# Module_I2C_Servo.net
KiCad netlist of a schematic drawn in EAGLE
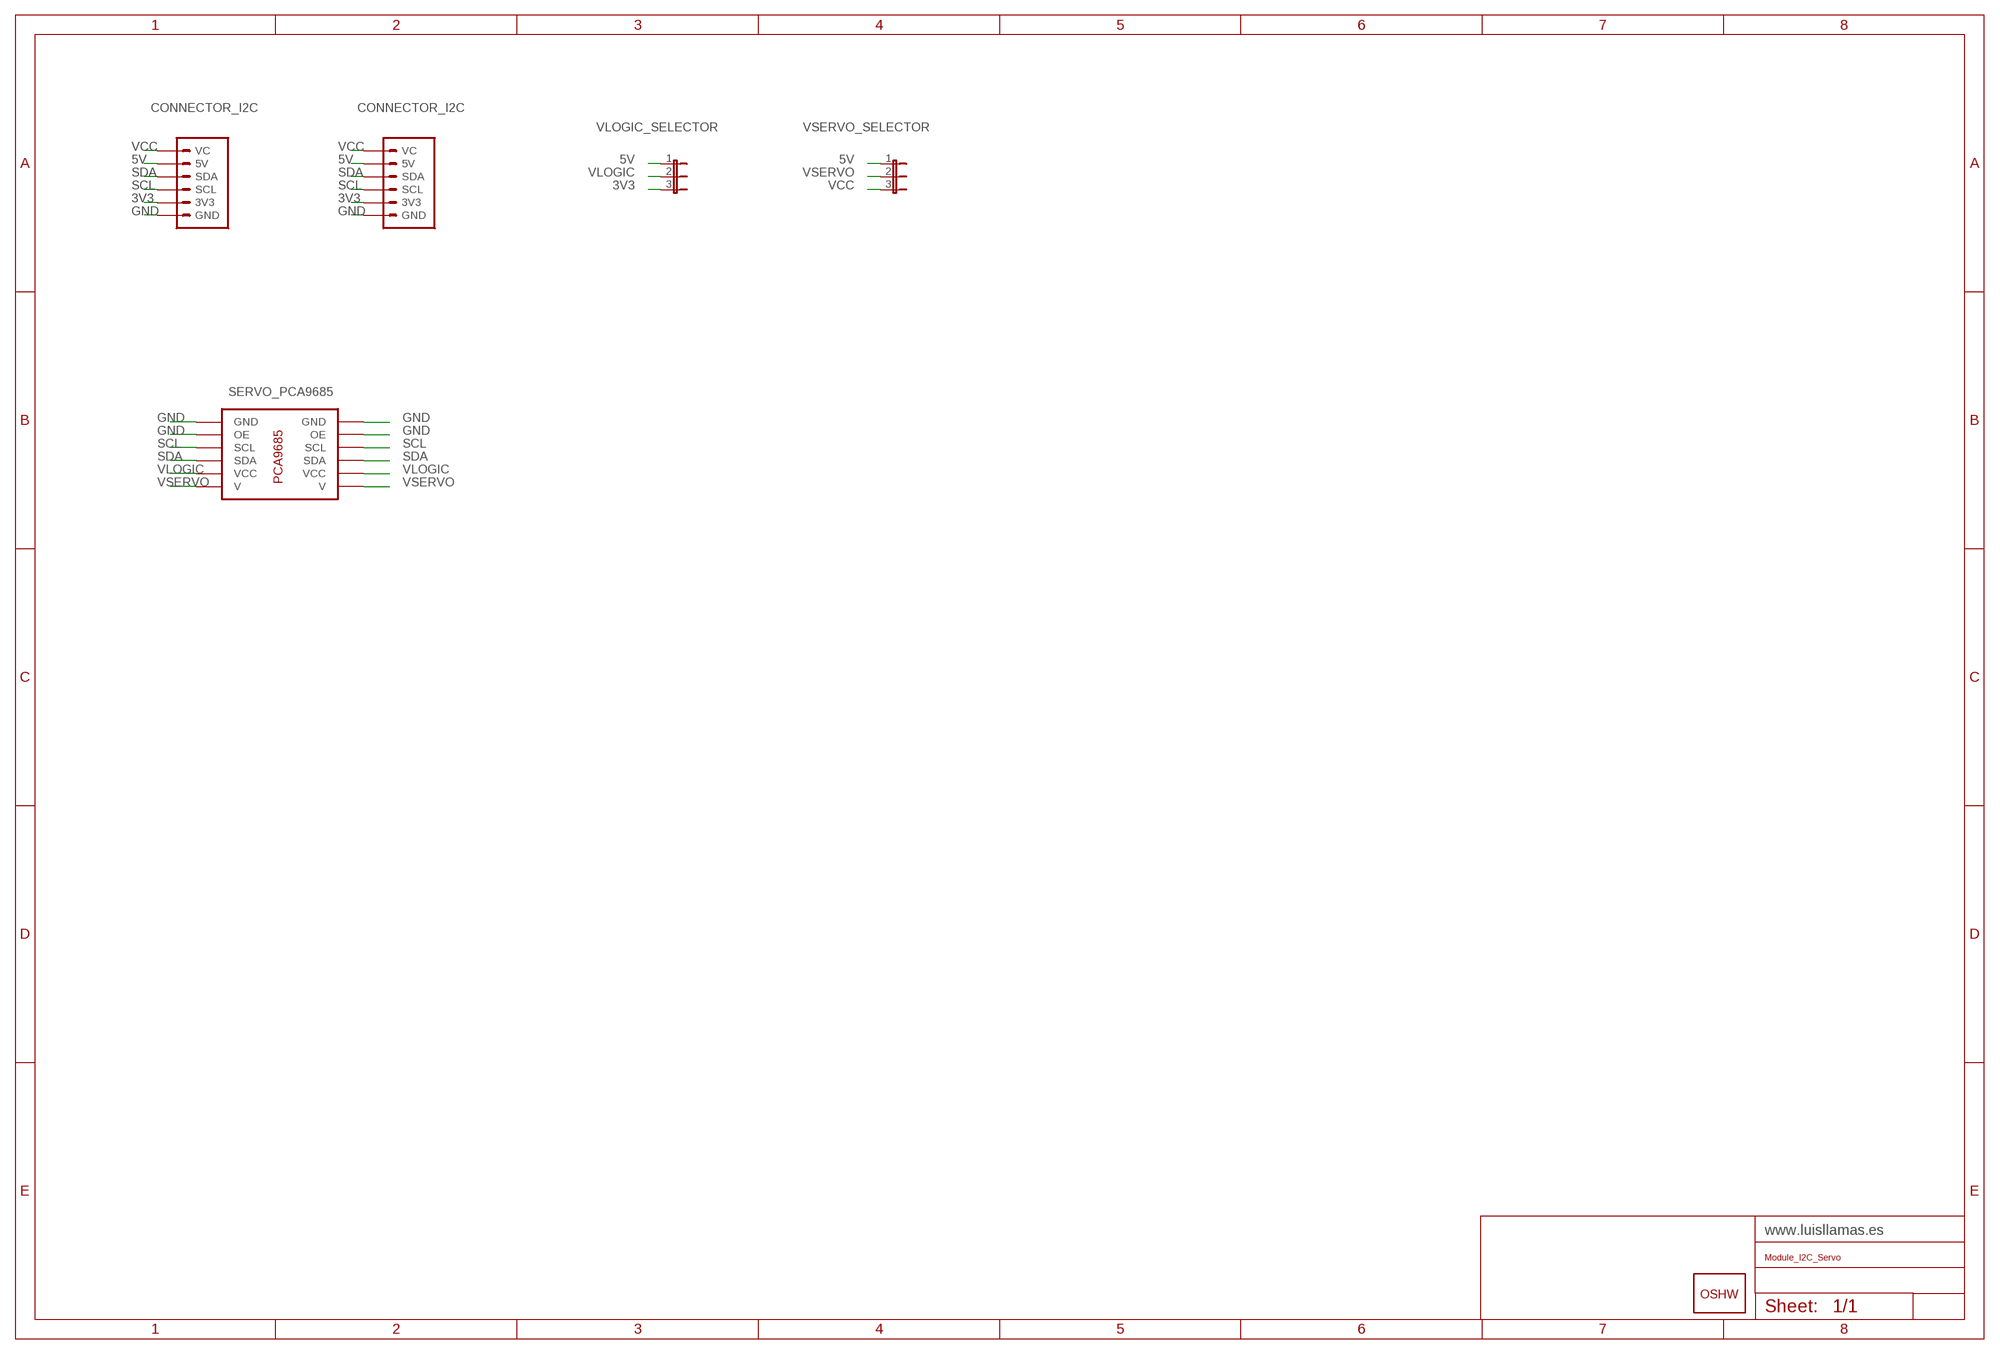
[diagram p0: schematic, sheet 1]

(export (version "E")
  (design (tool "Eeschema 10.0.6"))
  (components
    (comp (ref "GOLD_ORB_SM1")
      (value "OSHWLOGO_GOLD_ORB_MED")
      (footprint "eagle-import:OSHW1")
      (libsource (lib "eagle-import") (part "OSHWLOGO_GOLD_ORB_MED"))
    )
    (comp (ref "U$2")
      (value "SERVO_PCA9685")
      (footprint "eagle-import:SERVO_PCA9685")
      (libsource (lib "eagle-import") (part "SERVO_PCA9685"))
    )
    (comp (ref "U$3")
      (value "CONNECTOR_I2C")
      (footprint "eagle-import:CONNECTOR_I2C")
      (libsource (lib "eagle-import") (part "CONNECTOR_I2C"))
    )
    (comp (ref "U$4")
      (value "CONNECTOR_I2C")
      (footprint "eagle-import:CONNECTOR_I2C")
      (libsource (lib "eagle-import") (part "CONNECTOR_I2C"))
    )
    (comp (ref "VLOGIC_SELECTOR")
      (value "JUMPER_3")
      (footprint "eagle-import:JUMPER_3")
      (libsource (lib "eagle-import") (part "JUMPER_3"))
    )
    (comp (ref "VSERVO_SELECTOR")
      (value "JUMPER_3")
      (footprint "eagle-import:JUMPER_3")
      (libsource (lib "eagle-import") (part "JUMPER_3"))
    )
  )
  (nets
    (net (code "1") (name "/3V3") (class "Default")
      (node (ref "U$3") (pin "3V3") (pinfunction "3V3_3V3") (pintype "passive"))
      (node (ref "U$4") (pin "3V3") (pinfunction "3V3_3V3") (pintype "passive"))
      (node (ref "VLOGIC_SELECTOR") (pin "3") (pinfunction "3_3") (pintype "passive"))
    )
    (net (code "2") (name "/5V") (class "Default")
      (node (ref "U$3") (pin "5V") (pinfunction "5V_5V") (pintype "passive"))
      (node (ref "U$4") (pin "5V") (pinfunction "5V_5V") (pintype "passive"))
      (node (ref "VLOGIC_SELECTOR") (pin "1") (pinfunction "1_1") (pintype "passive"))
      (node (ref "VSERVO_SELECTOR") (pin "1") (pinfunction "1_1") (pintype "passive"))
    )
    (net (code "3") (name "/GND") (class "Default")
      (node (ref "U$2") (pin "GND@0") (pinfunction "GND_GND@0") (pintype "power_in"))
      (node (ref "U$2") (pin "GND@1") (pinfunction "GND_GND@1") (pintype "power_in"))
      (node (ref "U$2") (pin "OE@0") (pinfunction "OE_OE@0") (pintype "bidirectional"))
      (node (ref "U$2") (pin "OE@1") (pinfunction "OE_OE@1") (pintype "bidirectional"))
      (node (ref "U$3") (pin "GND") (pinfunction "GND_GND") (pintype "passive"))
      (node (ref "U$4") (pin "GND") (pinfunction "GND_GND") (pintype "passive"))
    )
    (net (code "4") (name "/SCL") (class "Default")
      (node (ref "U$2") (pin "SCL@0") (pinfunction "SCL_SCL@0") (pintype "bidirectional"))
      (node (ref "U$2") (pin "SCL@1") (pinfunction "SCL_SCL@1") (pintype "bidirectional"))
      (node (ref "U$3") (pin "SCL") (pinfunction "SCL_SCL") (pintype "passive"))
      (node (ref "U$4") (pin "SCL") (pinfunction "SCL_SCL") (pintype "passive"))
    )
    (net (code "5") (name "/SDA") (class "Default")
      (node (ref "U$2") (pin "SDA@0") (pinfunction "SDA_SDA@0") (pintype "bidirectional"))
      (node (ref "U$2") (pin "SDA@1") (pinfunction "SDA_SDA@1") (pintype "bidirectional"))
      (node (ref "U$3") (pin "SDA") (pinfunction "SDA_SDA") (pintype "passive"))
      (node (ref "U$4") (pin "SDA") (pinfunction "SDA_SDA") (pintype "passive"))
    )
    (net (code "6") (name "/VCC") (class "Default")
      (node (ref "U$3") (pin "VC") (pinfunction "VC_VC") (pintype "passive"))
      (node (ref "U$4") (pin "VC") (pinfunction "VC_VC") (pintype "passive"))
      (node (ref "VSERVO_SELECTOR") (pin "3") (pinfunction "3_3") (pintype "passive"))
    )
    (net (code "7") (name "/VLOGIC") (class "Default")
      (node (ref "U$2") (pin "VCC@0") (pinfunction "VCC_VCC@0") (pintype "power_in"))
      (node (ref "U$2") (pin "VCC@1") (pinfunction "VCC_VCC@1") (pintype "power_in"))
      (node (ref "VLOGIC_SELECTOR") (pin "2") (pinfunction "2_2") (pintype "passive"))
    )
    (net (code "8") (name "/VSERVO") (class "Default")
      (node (ref "U$2") (pin "VSERVO@0") (pinfunction "V_VSERVO@0") (pintype "power_in"))
      (node (ref "U$2") (pin "VSERVO@1") (pinfunction "V_VSERVO@1") (pintype "power_in"))
      (node (ref "VSERVO_SELECTOR") (pin "2") (pinfunction "2_2") (pintype "passive"))
    )
  )
)
